# TSST8.net
KiCad netlist of a schematic drawn in EAGLE
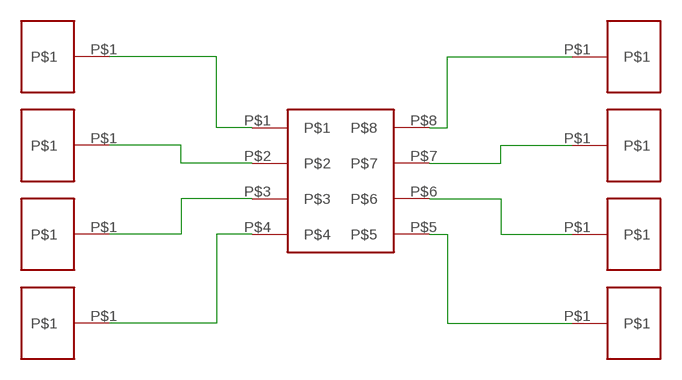
[diagram p0: schematic, sheet 1]

(export (version "E")
  (design (tool "Eeschema 10.0.6"))
  (components
    (comp (ref "U$1")
      (value "TSST8")
      (footprint "eagle-import:TSST8")
      (libsource (lib "eagle-import") (part "TSST8"))
    )
    (comp (ref "U$2")
      (value "PAD50X100MIL")
      (footprint "eagle-import:100X50MIL_PAD")
      (libsource (lib "eagle-import") (part "PAD50X100MIL"))
    )
    (comp (ref "U$3")
      (value "PAD50X100MIL")
      (footprint "eagle-import:100X50MIL_PAD")
      (libsource (lib "eagle-import") (part "PAD50X100MIL"))
    )
    (comp (ref "U$4")
      (value "PAD50X100MIL")
      (footprint "eagle-import:100X50MIL_PAD")
      (libsource (lib "eagle-import") (part "PAD50X100MIL"))
    )
    (comp (ref "U$5")
      (value "PAD50X100MIL")
      (footprint "eagle-import:100X50MIL_PAD")
      (libsource (lib "eagle-import") (part "PAD50X100MIL"))
    )
    (comp (ref "U$6")
      (value "PAD50X100MIL")
      (footprint "eagle-import:100X50MIL_PAD")
      (libsource (lib "eagle-import") (part "PAD50X100MIL"))
    )
    (comp (ref "U$7")
      (value "PAD50X100MIL")
      (footprint "eagle-import:100X50MIL_PAD")
      (libsource (lib "eagle-import") (part "PAD50X100MIL"))
    )
    (comp (ref "U$8")
      (value "PAD50X100MIL")
      (footprint "eagle-import:100X50MIL_PAD")
      (libsource (lib "eagle-import") (part "PAD50X100MIL"))
    )
    (comp (ref "U$9")
      (value "PAD50X100MIL")
      (footprint "eagle-import:100X50MIL_PAD")
      (libsource (lib "eagle-import") (part "PAD50X100MIL"))
    )
  )
  (nets
    (net (code "1") (name "Net-(U$1-PadP$1)") (class "Default")
      (node (ref "U$1") (pin "P$1") (pinfunction "P$1_P$1") (pintype "bidirectional"))
      (node (ref "U$2") (pin "P$1") (pinfunction "P$1_P$1") (pintype "bidirectional"))
    )
    (net (code "2") (name "Net-(U$1-PadP$2)") (class "Default")
      (node (ref "U$1") (pin "P$2") (pinfunction "P$2_P$2") (pintype "bidirectional"))
      (node (ref "U$3") (pin "P$1") (pinfunction "P$1_P$1") (pintype "bidirectional"))
    )
    (net (code "3") (name "Net-(U$1-PadP$3)") (class "Default")
      (node (ref "U$1") (pin "P$3") (pinfunction "P$3_P$3") (pintype "bidirectional"))
      (node (ref "U$4") (pin "P$1") (pinfunction "P$1_P$1") (pintype "bidirectional"))
    )
    (net (code "4") (name "Net-(U$1-PadP$4)") (class "Default")
      (node (ref "U$1") (pin "P$4") (pinfunction "P$4_P$4") (pintype "bidirectional"))
      (node (ref "U$5") (pin "P$1") (pinfunction "P$1_P$1") (pintype "bidirectional"))
    )
    (net (code "5") (name "Net-(U$1-PadP$5)") (class "Default")
      (node (ref "U$1") (pin "P$5") (pinfunction "P$5_P$5") (pintype "bidirectional"))
      (node (ref "U$6") (pin "P$1") (pinfunction "P$1_P$1") (pintype "bidirectional"))
    )
    (net (code "6") (name "Net-(U$1-PadP$6)") (class "Default")
      (node (ref "U$1") (pin "P$6") (pinfunction "P$6_P$6") (pintype "bidirectional"))
      (node (ref "U$7") (pin "P$1") (pinfunction "P$1_P$1") (pintype "bidirectional"))
    )
    (net (code "7") (name "Net-(U$1-PadP$7)") (class "Default")
      (node (ref "U$1") (pin "P$7") (pinfunction "P$7_P$7") (pintype "bidirectional"))
      (node (ref "U$8") (pin "P$1") (pinfunction "P$1_P$1") (pintype "bidirectional"))
    )
    (net (code "8") (name "Net-(U$1-PadP$8)") (class "Default")
      (node (ref "U$1") (pin "P$8") (pinfunction "P$8_P$8") (pintype "bidirectional"))
      (node (ref "U$9") (pin "P$1") (pinfunction "P$1_P$1") (pintype "bidirectional"))
    )
  )
)
